# M5amigo-CAN-BUS.net
KiCad netlist of a schematic drawn in EAGLE
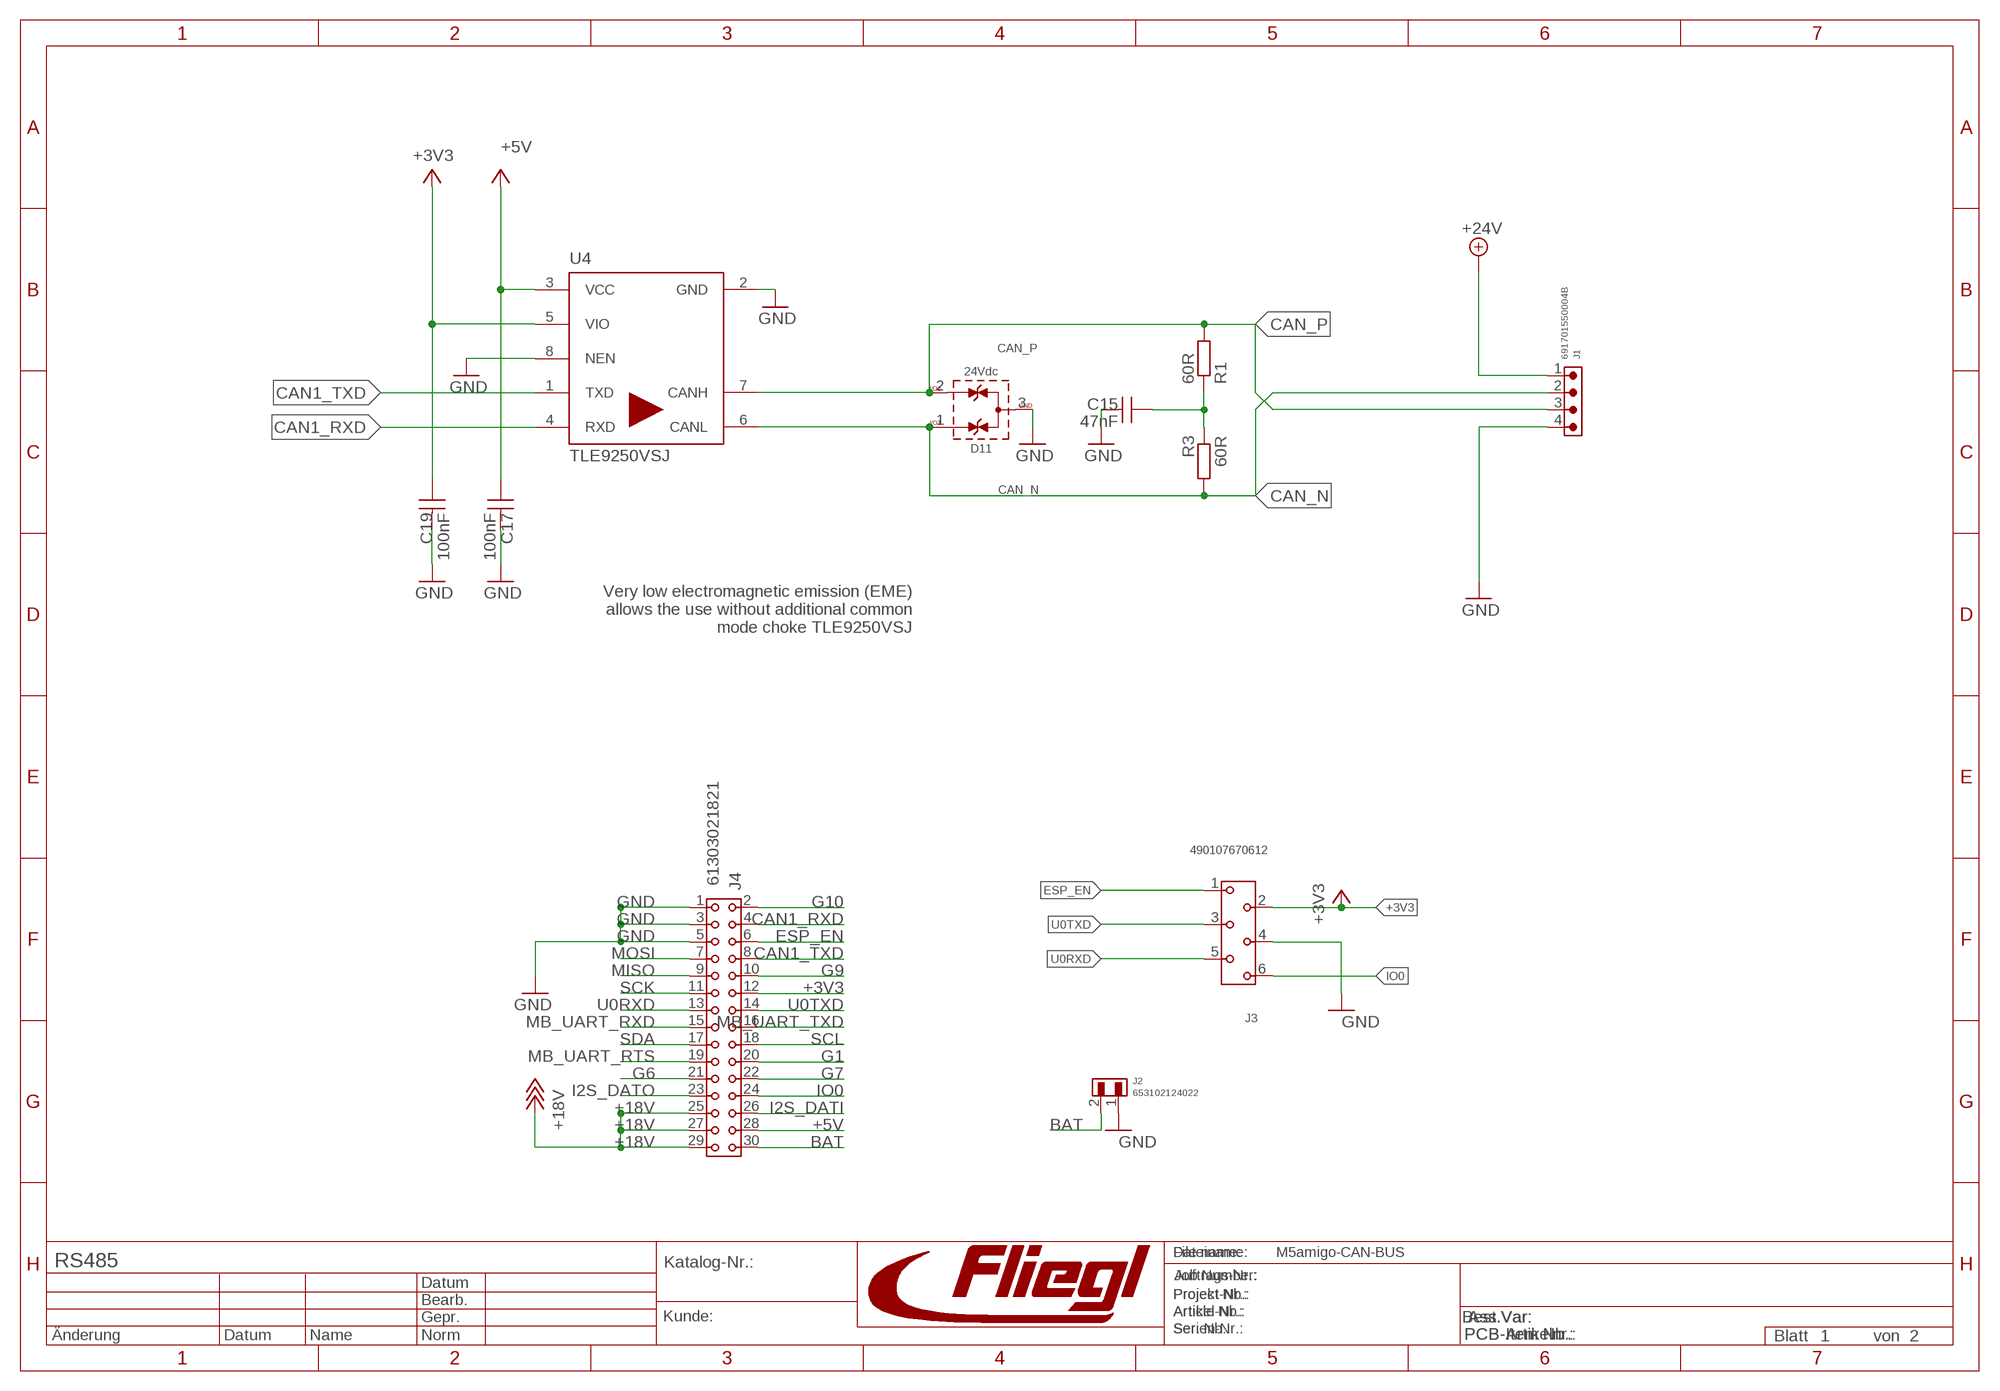
[diagram p0: schematic, sheet 1]
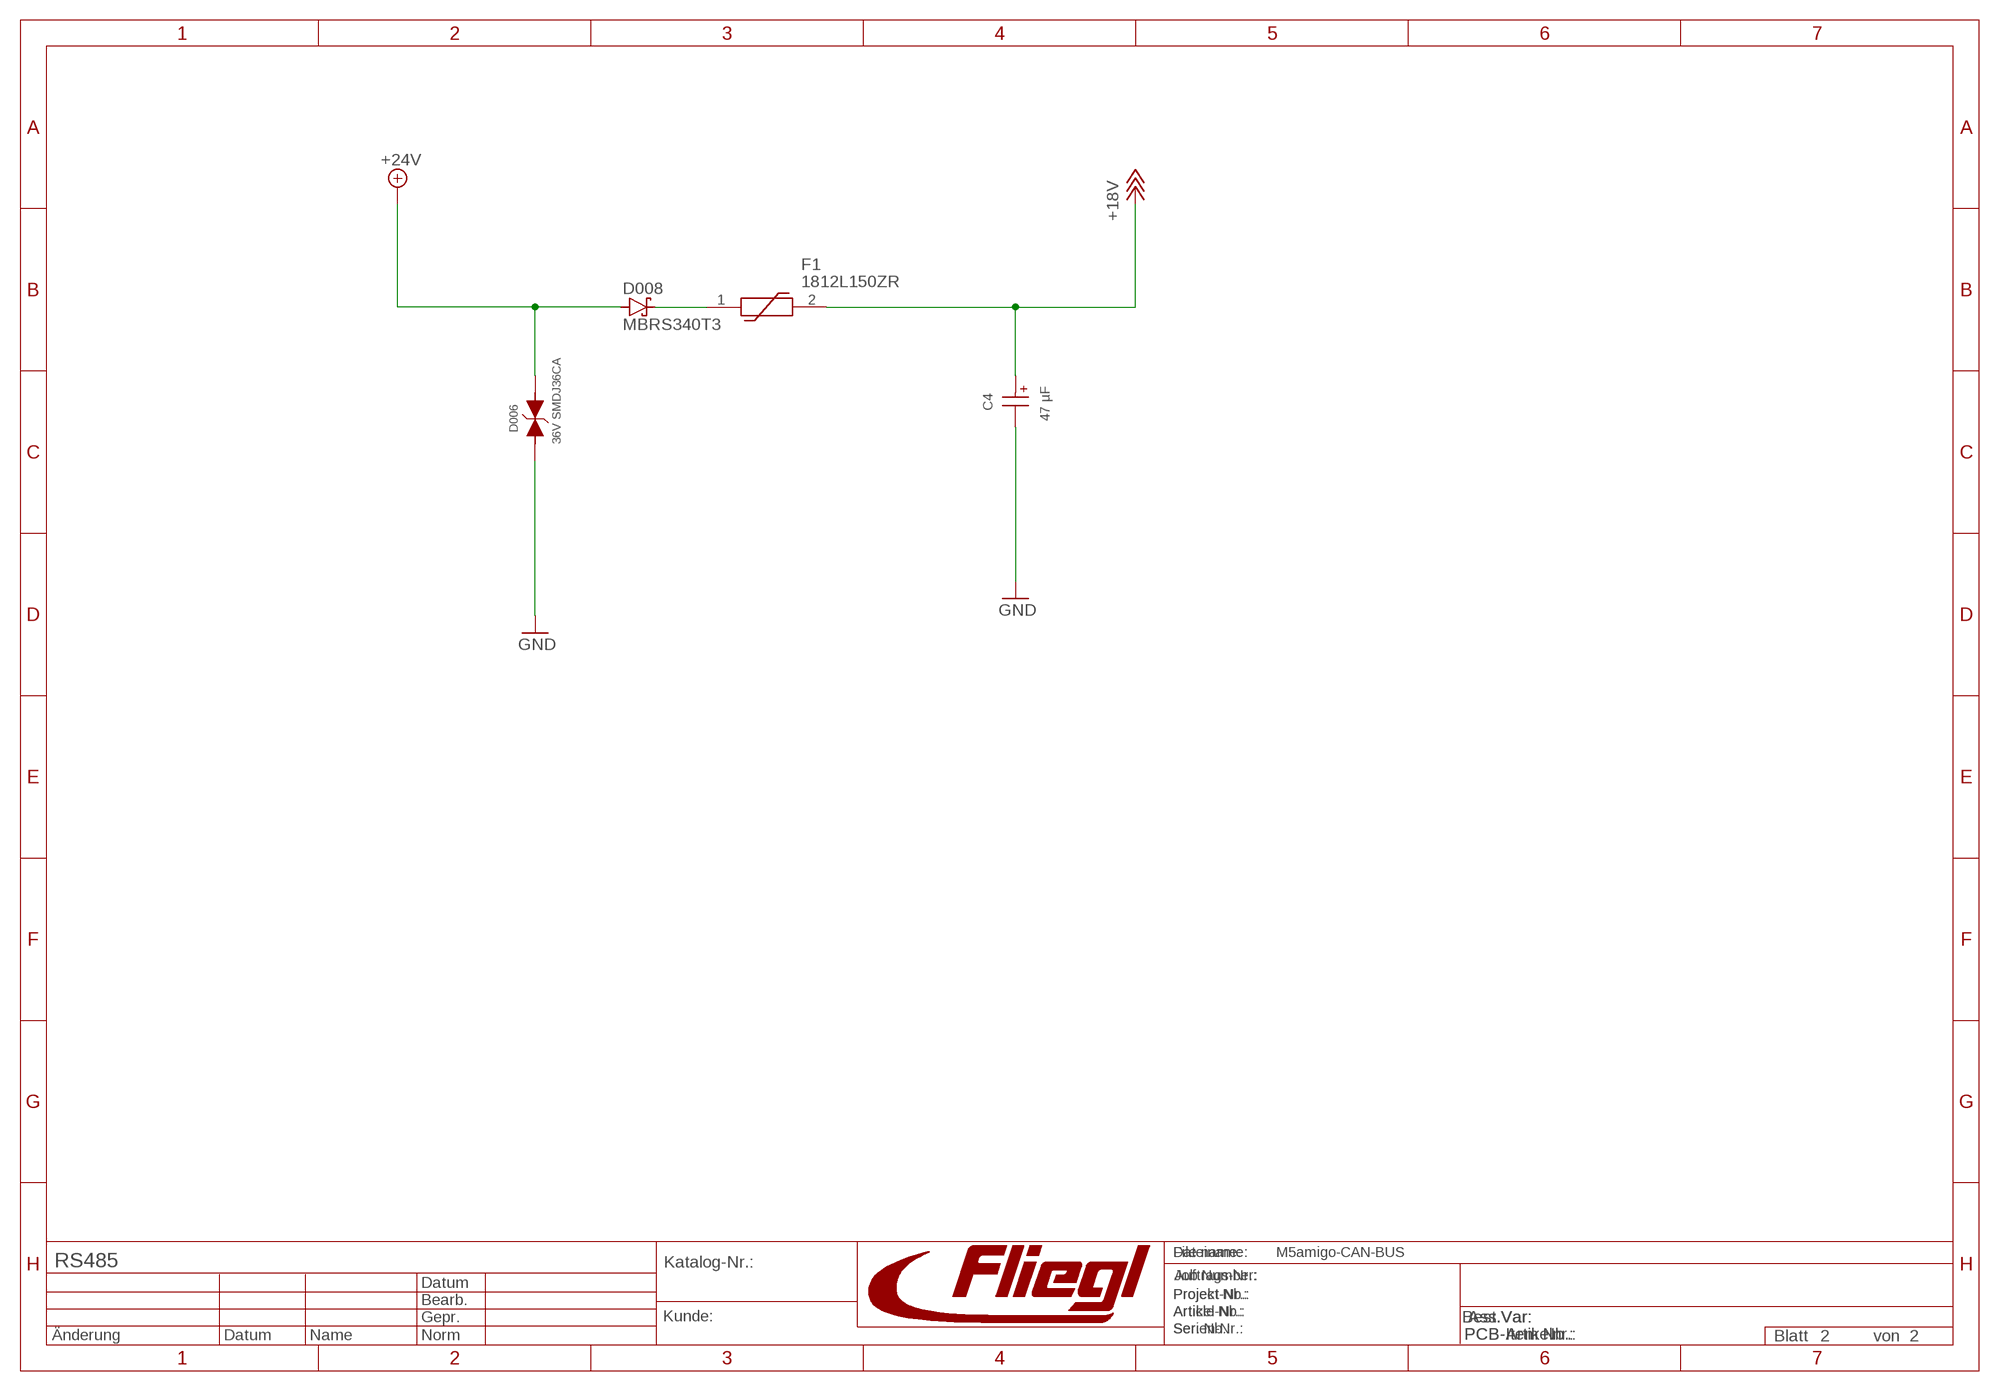
[diagram p1: schematic, sheet 2]

(export (version "E")
  (design (tool "Eeschema 10.0.6"))
  (components
    (comp (ref "C15")
      (value "47nF")
      (footprint "eagle-import:WCAP-CSGP_0805_H0.8_R")
      (libsource (lib "eagle-import") (part "WCAP-CSGP_0805_H0.8_50V(DC)_R_885012207096"))
    )
    (comp (ref "C17")
      (value "100nF")
      (footprint "eagle-import:WCAP-CSGP_0805_H0.8_R")
      (libsource (lib "eagle-import") (part "WCAP-CSGP_0805_H0.8_50V(DC)_R_885012207098"))
    )
    (comp (ref "C19")
      (value "100nF")
      (footprint "eagle-import:WCAP-CSGP_0805_H0.8_R")
      (libsource (lib "eagle-import") (part "WCAP-CSGP_0805_H0.8_50V(DC)_R_885012207098"))
    )
    (comp (ref "D11")
      (value "24Vdc")
      (footprint "eagle-import:WE-TVS_SOT23-3L")
      (libsource (lib "eagle-import") (part "WE-TVS_SOT23-3L_824094024"))
    )
    (comp (ref "J1")
      (value "691701550004B")
      (footprint "eagle-import:691701550004B")
      (libsource (lib "eagle-import") (part "691701550004B"))
    )
    (comp (ref "J2")
      (value "653102124022")
      (footprint "eagle-import:653102124022")
      (libsource (lib "eagle-import") (part "653102124022"))
    )
    (comp (ref "J3")
      (value "490107670612")
      (footprint "eagle-import:490107670612_DEBUGGING")
      (libsource (lib "eagle-import") (part "490107670612_DEBUGGING"))
    )
    (comp (ref "J4")
      (value "61303021821")
      (footprint "eagle-import:61303021821")
      (libsource (lib "eagle-import") (part "6130XX21821_61303021821"))
    )
    (comp (ref "R1")
      (value "60R")
      (footprint "eagle-import:R0805")
      (libsource (lib "eagle-import") (part "R-EU_R0805"))
    )
    (comp (ref "R3")
      (value "60R")
      (footprint "eagle-import:R0805")
      (libsource (lib "eagle-import") (part "R-EU_R0805"))
    )
    (comp (ref "U4")
      (value "TLE9250VSJ")
      (footprint "eagle-import:SOIC127P602X173-8N-V")
      (libsource (lib "eagle-import") (part "TLE9250VSJ"))
    )
    (comp (ref "C4")
      (value "47 µF")
      (footprint "eagle-import:WCAP-ASLL_6.3X7.7(DXL)")
      (libsource (lib "eagle-import") (part "WCAP-ASLL_6.3X7.7_865060645008"))
    )
    (comp (ref "D006")
      (value "36V SMDJ36CA")
      (footprint "eagle-import:WE-TVSP_DO-214AB_BIDIRECTIONAL")
      (libsource (lib "eagle-import") (part "WE-TVSP_DO-214AB_3000W_BI_824551361"))
    )
    (comp (ref "D008")
      (value "MBRS340T3")
      (footprint "eagle-import:SMC")
      (libsource (lib "eagle-import") (part "MBRS30T34"))
    )
    (comp (ref "F1")
      (value "1812L150ZR")
      (footprint "eagle-import:1812L010DR")
      (fields (field (name "MOUSER_PART_NUMBER") "576-1812L150ZR"))
      (libsource (lib "eagle-import") (part "1812L150ZR"))
    )
  )
  (nets
    (net (code "1") (name "+3V3") (class "Default")
      (node (ref "C19") (pin "1") (pinfunction "1_1") (pintype "passive"))
      (node (ref "J3") (pin "2") (pinfunction "2_2") (pintype "passive"))
      (node (ref "J4") (pin "12") (pinfunction "12_12") (pintype "passive"))
      (node (ref "U4") (pin "5") (pinfunction "VIO_5") (pintype "input"))
    )
    (net (code "2") (name "+5V") (class "Default")
      (node (ref "C17") (pin "1") (pinfunction "1_1") (pintype "passive"))
      (node (ref "J4") (pin "28") (pinfunction "28_28") (pintype "passive"))
      (node (ref "U4") (pin "3") (pinfunction "VCC_3") (pintype "input"))
    )
    (net (code "3") (name "+18V") (class "Default")
      (node (ref "C4") (pin "1") (pinfunction "+_1") (pintype "passive"))
      (node (ref "F1") (pin "2") (pinfunction "2_2") (pintype "bidirectional"))
      (node (ref "J4") (pin "25") (pinfunction "25_25") (pintype "passive"))
      (node (ref "J4") (pin "27") (pinfunction "27_27") (pintype "passive"))
      (node (ref "J4") (pin "29") (pinfunction "29_29") (pintype "passive"))
    )
    (net (code "4") (name "+24V") (class "Default")
      (node (ref "D006") (pin "2") (pinfunction "2_2") (pintype "passive"))
      (node (ref "D008") (pin "A") (pinfunction "A_A") (pintype "passive"))
      (node (ref "J1") (pin "1") (pinfunction "1_1") (pintype "passive"))
    )
    (net (code "5") (name "BAT") (class "Default")
      (node (ref "J2") (pin "2") (pinfunction "2_2") (pintype "passive"))
      (node (ref "J4") (pin "30") (pinfunction "30_30") (pintype "passive"))
    )
    (net (code "6") (name "CAN1_RXD") (class "Default")
      (node (ref "J4") (pin "4") (pinfunction "4_4") (pintype "passive"))
      (node (ref "U4") (pin "4") (pinfunction "RXD_4") (pintype "output"))
    )
    (net (code "7") (name "CAN1_TXD") (class "Default")
      (node (ref "J4") (pin "8") (pinfunction "8_8") (pintype "passive"))
      (node (ref "U4") (pin "1") (pinfunction "TXD_1") (pintype "input"))
    )
    (net (code "8") (name "CAN_N") (class "Default")
      (node (ref "D11") (pin "1") (pinfunction "I/O1_1") (pintype "passive"))
      (node (ref "J1") (pin "2") (pinfunction "2_2") (pintype "passive"))
      (node (ref "R3") (pin "2") (pinfunction "2_2") (pintype "passive"))
      (node (ref "U4") (pin "6") (pinfunction "CANL_6") (pintype "bidirectional"))
    )
    (net (code "9") (name "CAN_P") (class "Default")
      (node (ref "D11") (pin "2") (pinfunction "I/O2_2") (pintype "passive"))
      (node (ref "J1") (pin "3") (pinfunction "3_3") (pintype "passive"))
      (node (ref "R1") (pin "2") (pinfunction "2_2") (pintype "passive"))
      (node (ref "U4") (pin "7") (pinfunction "CANH_7") (pintype "bidirectional"))
    )
    (net (code "10") (name "ESP_EN") (class "Default")
      (node (ref "J3") (pin "1") (pinfunction "1_1") (pintype "passive"))
      (node (ref "J4") (pin "6") (pinfunction "6_6") (pintype "passive"))
    )
    (net (code "11") (name "G1") (class "Default")
      (node (ref "J4") (pin "20") (pinfunction "20_20") (pintype "passive"))
    )
    (net (code "12") (name "G6") (class "Default")
      (node (ref "J4") (pin "21") (pinfunction "21_21") (pintype "passive"))
    )
    (net (code "13") (name "G7") (class "Default")
      (node (ref "J4") (pin "22") (pinfunction "22_22") (pintype "passive"))
    )
    (net (code "14") (name "G9") (class "Default")
      (node (ref "J4") (pin "10") (pinfunction "10_10") (pintype "passive"))
    )
    (net (code "15") (name "G10") (class "Default")
      (node (ref "J4") (pin "2") (pinfunction "2_2") (pintype "passive"))
    )
    (net (code "16") (name "GND") (class "Default")
      (node (ref "C15") (pin "2") (pinfunction "2_2") (pintype "passive"))
      (node (ref "C17") (pin "2") (pinfunction "2_2") (pintype "passive"))
      (node (ref "C19") (pin "2") (pinfunction "2_2") (pintype "passive"))
      (node (ref "C4") (pin "2") (pinfunction "-_2") (pintype "passive"))
      (node (ref "D006") (pin "1") (pinfunction "1_1") (pintype "passive"))
      (node (ref "D11") (pin "3") (pinfunction "GND_3") (pintype "passive"))
      (node (ref "J1") (pin "4") (pinfunction "4_4") (pintype "passive"))
      (node (ref "J2") (pin "1") (pinfunction "1_1") (pintype "passive"))
      (node (ref "J3") (pin "4") (pinfunction "4_4") (pintype "passive"))
      (node (ref "J4") (pin "1") (pinfunction "1_1") (pintype "passive"))
      (node (ref "J4") (pin "3") (pinfunction "3_3") (pintype "passive"))
      (node (ref "J4") (pin "5") (pinfunction "5_5") (pintype "passive"))
      (node (ref "U4") (pin "2") (pinfunction "GND_2") (pintype "power_in"))
      (node (ref "U4") (pin "8") (pinfunction "NEN_8") (pintype "input"))
    )
    (net (code "17") (name "I2S_DATI") (class "Default")
      (node (ref "J4") (pin "26") (pinfunction "26_26") (pintype "passive"))
    )
    (net (code "18") (name "I2S_DATO") (class "Default")
      (node (ref "J4") (pin "23") (pinfunction "23_23") (pintype "passive"))
    )
    (net (code "19") (name "IO0") (class "Default")
      (node (ref "J3") (pin "6") (pinfunction "6_6") (pintype "passive"))
      (node (ref "J4") (pin "24") (pinfunction "24_24") (pintype "passive"))
    )
    (net (code "20") (name "MB_UART_RTS") (class "Default")
      (node (ref "J4") (pin "19") (pinfunction "19_19") (pintype "passive"))
    )
    (net (code "21") (name "MB_UART_RXD") (class "Default")
      (node (ref "J4") (pin "15") (pinfunction "15_15") (pintype "passive"))
    )
    (net (code "22") (name "MB_UART_TXD") (class "Default")
      (node (ref "J4") (pin "16") (pinfunction "16_16") (pintype "passive"))
    )
    (net (code "23") (name "MISO") (class "Default")
      (node (ref "J4") (pin "9") (pinfunction "9_9") (pintype "passive"))
    )
    (net (code "24") (name "MOSI") (class "Default")
      (node (ref "J4") (pin "7") (pinfunction "7_7") (pintype "passive"))
    )
    (net (code "25") (name "Net-(C15-Pad1)") (class "Default")
      (node (ref "C15") (pin "1") (pinfunction "1_1") (pintype "passive"))
      (node (ref "R1") (pin "1") (pinfunction "1_1") (pintype "passive"))
      (node (ref "R3") (pin "1") (pinfunction "1_1") (pintype "passive"))
    )
    (net (code "26") (name "Net-(D008-PadC)") (class "Default")
      (node (ref "D008") (pin "C") (pinfunction "C_C") (pintype "passive"))
      (node (ref "F1") (pin "1") (pinfunction "1_1") (pintype "bidirectional"))
    )
    (net (code "27") (name "SCK") (class "Default")
      (node (ref "J4") (pin "11") (pinfunction "11_11") (pintype "passive"))
    )
    (net (code "28") (name "SCL") (class "Default")
      (node (ref "J4") (pin "18") (pinfunction "18_18") (pintype "passive"))
    )
    (net (code "29") (name "SDA") (class "Default")
      (node (ref "J4") (pin "17") (pinfunction "17_17") (pintype "passive"))
    )
    (net (code "30") (name "U0RXD") (class "Default")
      (node (ref "J3") (pin "5") (pinfunction "5_5") (pintype "passive"))
      (node (ref "J4") (pin "13") (pinfunction "13_13") (pintype "passive"))
    )
    (net (code "31") (name "U0TXD") (class "Default")
      (node (ref "J3") (pin "3") (pinfunction "3_3") (pintype "passive"))
      (node (ref "J4") (pin "14") (pinfunction "14_14") (pintype "passive"))
    )
  )
)
